# Sheet1___VL53L0X.net
KiCad netlist of a schematic drawn in Altium Designer
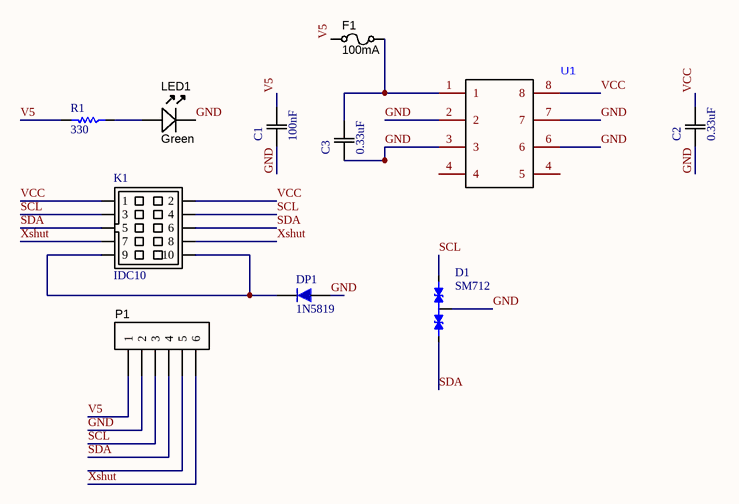
[diagram p0: Sheet1___VL53L0X.SchDoc]

(export (version "E")
  (design (tool "Eeschema 10.0.6"))
  (components
    (comp (ref "C1")
      (value "100nF")
      (footprint "0805")
      (description "CAP CER 0.1UF 50V X7R 0805")
      (fields (field (name "TOLERANCE") "10%"))
      (libsource (lib "AltiumLibraries") (part "CAP 470nF 50V"))
    )
    (comp (ref "C2")
      (value "0.33uF")
      (footprint "0805")
      (description "CAP CER 0.1UF 50V X7R 0805")
      (fields (field (name "TOLERANCE") "10%"))
      (libsource (lib "AltiumLibraries") (part "CAP 470nF 50V"))
    )
    (comp (ref "C3")
      (value "0.33uF")
      (footprint "0805")
      (description "CAP CER 0.1UF 50V X7R 0805")
      (fields (field (name "TOLERANCE") "10%"))
      (libsource (lib "AltiumLibraries") (part "CAP 470nF 50V"))
    )
    (comp (ref "D1")
      (value "SM712")
      (footprint "psm712")
      (description "Asymmetrical TVS Diode for  Extended Common-Mode RS-485")
      (fields (field (name "MANUFACTURER") "SEMTECH") (field (name "MANUFACTURE PART #") "SM712.TC"))
      (libsource (lib "Diode") (part "SM712.TC"))
    )
    (comp (ref "DP1")
      (value "1N5819")
      (footprint "430X270D")
      (description "Schottkey Rectifiers")
      (fields (field (name "DESIGNER") "Abbas Basereh"))
      (libsource (lib "Altium") (part "1N5819"))
    )
    (comp (ref "F1")
      (value "100mA")
      (footprint "RESC3216X70N")
      (description "Fuse 160mA 63VDC 1206 SMD")
      (fields (field (name "Comment") "Slow-blow"))
      (libsource (lib "BPL_Library") (part "FUSE_160mA_1206"))
    )
    (comp (ref "K1")
      (value "IDC10")
      (footprint "IDC10-B")
      (description "BOXHEADER 10 PIN")
      (fields
        (field (name "MANUFACTURER") "Assmann Electronics Inc")
        (field (name "MANUFACTURER PART NUMBER") "AWHW10G-0202-T-R")
      )
      (libsource (lib "vh_altium_library") (part "IDC10"))
    )
    (comp (ref "LED1")
      (value "~")
      (footprint "LED-0805-K")
      (description "LED, 0805 SMD, Green")
      (fields (field (name "COLOR") "Green"))
      (libsource (lib "BPL_Library") (part "LED_SMD_Green_0805_6mcd"))
    )
    (comp (ref "P1")
      (value "Header 6pin")
      (footprint "HDR1X6")
      (description "Header, 6-pin")
      (libsource (lib "BPL_Library") (part "Header6P"))
    )
    (comp (ref "R1")
      (value "330")
      (footprint "RES 0805 (2012X06L)")
      (description "Resistor")
      (fields (field (name "TOLERANCE") "5%") (field (name "POWER") "1/8 W"))
      (libsource (lib "Electrovolt Lib") (part "Resistor"))
    )
    (comp (ref "U1")
      (value "~")
      (footprint "78L05CD15V5V_LIB")
      (libsource (lib "altium-import") (part "root_0_MC78L05ACDG 5V Regulator_"))
    )
  )
  (nets
    (net (code "1") (name "/GND") (class "Default")
      (node (ref "C1") (pin "1") (pinfunction "C1_1") (pintype "passive"))
      (node (ref "C2") (pin "1") (pinfunction "C1_1") (pintype "passive"))
      (node (ref "C3") (pin "1") (pinfunction "C1_1") (pintype "passive"))
      (node (ref "D1") (pin "3") (pinfunction "3_3") (pintype "passive"))
      (node (ref "DP1") (pin "1") (pintype "passive"))
      (node (ref "LED1") (pin "K") (pinfunction "K_K") (pintype "passive"))
      (node (ref "P1") (pin "2") (pinfunction "2_2") (pintype "passive"))
      (node (ref "U1") (pin "2") (pinfunction "2_2") (pintype "passive"))
      (node (ref "U1") (pin "3") (pinfunction "3_3") (pintype "passive"))
      (node (ref "U1") (pin "6") (pinfunction "6_6") (pintype "passive"))
      (node (ref "U1") (pin "7") (pinfunction "7_7") (pintype "passive"))
    )
    (net (code "2") (name "/SCL") (class "Default")
      (node (ref "D1") (pin "1") (pinfunction "1_1") (pintype "passive"))
      (node (ref "K1") (pin "3") (pinfunction "3_3") (pintype "passive"))
      (node (ref "K1") (pin "4") (pinfunction "4_4") (pintype "passive"))
      (node (ref "P1") (pin "3") (pinfunction "3_3") (pintype "passive"))
    )
    (net (code "3") (name "/SDA") (class "Default")
      (node (ref "D1") (pin "2") (pinfunction "2_2") (pintype "passive"))
      (node (ref "K1") (pin "5") (pinfunction "5_5") (pintype "passive"))
      (node (ref "K1") (pin "6") (pinfunction "6_6") (pintype "passive"))
      (node (ref "P1") (pin "4") (pinfunction "4_4") (pintype "passive"))
    )
    (net (code "4") (name "/V5") (class "Default")
      (node (ref "C1") (pin "2") (pinfunction "C2_2") (pintype "passive"))
      (node (ref "F1") (pin "2") (pinfunction "2_2") (pintype "passive"))
      (node (ref "P1") (pin "1") (pinfunction "1_1") (pintype "passive"))
      (node (ref "R1") (pin "2") (pinfunction "2_2") (pintype "passive"))
    )
    (net (code "5") (name "/VCC") (class "Default")
      (node (ref "C2") (pin "2") (pinfunction "C2_2") (pintype "passive"))
      (node (ref "K1") (pin "1") (pinfunction "1_1") (pintype "passive"))
      (node (ref "K1") (pin "2") (pinfunction "2_2") (pintype "passive"))
      (node (ref "U1") (pin "8") (pinfunction "8_8") (pintype "passive"))
    )
    (net (code "6") (name "/Xshut") (class "Default")
      (node (ref "K1") (pin "7") (pinfunction "7_7") (pintype "passive"))
      (node (ref "K1") (pin "8") (pinfunction "8_8") (pintype "passive"))
      (node (ref "P1") (pin "6") (pinfunction "6_6") (pintype "passive"))
    )
    (net (code "7") (name "Net-(C3-C2)") (class "Default")
      (node (ref "C3") (pin "2") (pinfunction "C2_2") (pintype "passive"))
      (node (ref "F1") (pin "1") (pinfunction "1_1") (pintype "passive"))
      (node (ref "U1") (pin "1") (pinfunction "1_1") (pintype "passive"))
    )
    (net (code "8") (name "Net-(DP1-Pad2)") (class "Default")
      (node (ref "DP1") (pin "2") (pintype "passive"))
      (node (ref "K1") (pin "10") (pinfunction "10_10") (pintype "passive"))
      (node (ref "K1") (pin "9") (pinfunction "9_9") (pintype "passive"))
    )
    (net (code "9") (name "Net-(LED1-PadA)") (class "Default")
      (node (ref "LED1") (pin "A") (pinfunction "A_A") (pintype "passive"))
      (node (ref "R1") (pin "1") (pinfunction "1_1") (pintype "passive"))
    )
    (net (code "10") (name "unconnected-(P1-Pad5)") (class "Default")
      (node (ref "P1") (pin "5") (pinfunction "5_5") (pintype "passive"))
    )
    (net (code "11") (name "unconnected-(U1-5-Pad4)") (class "Default")
      (node (ref "U1") (pin "4") (pinfunction "5_4") (pintype "passive"))
    )
    (net (code "12") (name "unconnected-(U1-Pad4)") (class "Default")
      (node (ref "U1") (pin "4") (pinfunction "4_4") (pintype "passive"))
    )
  )
)
